# LT3060XTS8_45V_to_1V8.net
KiCad netlist of a schematic drawn in EAGLE
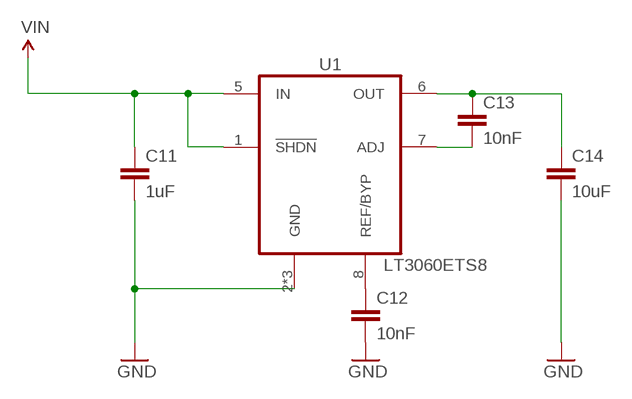
[diagram p0: schematic, sheet 1]

(export (version "E")
  (design (tool "Eeschema 10.0.6"))
  (components
    (comp (ref "C11")
      (value "1uF")
      (footprint "eagle-import:C0402")
      (libsource (lib "eagle-import") (part "C-EUC0402"))
    )
    (comp (ref "C12")
      (value "10nF")
      (footprint "eagle-import:C0402")
      (libsource (lib "eagle-import") (part "C-EUC0402"))
    )
    (comp (ref "C13")
      (value "10nF")
      (footprint "eagle-import:C0402")
      (libsource (lib "eagle-import") (part "C-EUC0402"))
    )
    (comp (ref "C14")
      (value "10uF")
      (footprint "eagle-import:C0402")
      (libsource (lib "eagle-import") (part "C-EUC0402"))
    )
    (comp (ref "U1")
      (value "LT3060ETS8")
      (footprint "eagle-import:LINEAR_TS8")
      (libsource (lib "eagle-import") (part "LT3060TS8E"))
    )
  )
  (nets
    (net (code "1") (name "GND") (class "Default")
      (node (ref "C11") (pin "2") (pinfunction "2_2") (pintype "passive"))
      (node (ref "C12") (pin "2") (pinfunction "2_2") (pintype "passive"))
      (node (ref "C14") (pin "2") (pinfunction "2_2") (pintype "passive"))
      (node (ref "U1") (pin "2") (pinfunction "GND_2") (pintype "passive"))
      (node (ref "U1") (pin "3") (pinfunction "GND_3") (pintype "passive"))
      (node (ref "U1") (pin "4") (pinfunction "GND_4") (pintype "passive"))
    )
    (net (code "2") (name "Net-(U1-ADJ)") (class "Default")
      (node (ref "C13") (pin "2") (pinfunction "2_2") (pintype "passive"))
      (node (ref "U1") (pin "7") (pinfunction "ADJ_7") (pintype "input"))
    )
    (net (code "3") (name "Net-(U1-OUT)") (class "Default")
      (node (ref "C13") (pin "1") (pinfunction "1_1") (pintype "passive"))
      (node (ref "C14") (pin "1") (pinfunction "1_1") (pintype "passive"))
      (node (ref "U1") (pin "6") (pinfunction "OUT_6") (pintype "power_in"))
    )
    (net (code "4") (name "Net-(U1-REF{slash}BYP)") (class "Default")
      (node (ref "C12") (pin "1") (pinfunction "1_1") (pintype "passive"))
      (node (ref "U1") (pin "8") (pinfunction "REF/BYP_8") (pintype "input"))
    )
    (net (code "5") (name "VIN") (class "Default")
      (node (ref "C11") (pin "1") (pinfunction "1_1") (pintype "passive"))
      (node (ref "U1") (pin "1") (pinfunction "~{SHDN}_1") (pintype "input"))
      (node (ref "U1") (pin "5") (pinfunction "IN_5") (pintype "power_in"))
    )
  )
)
